# Connection.net
KiCad netlist of a schematic drawn in Altium Designer
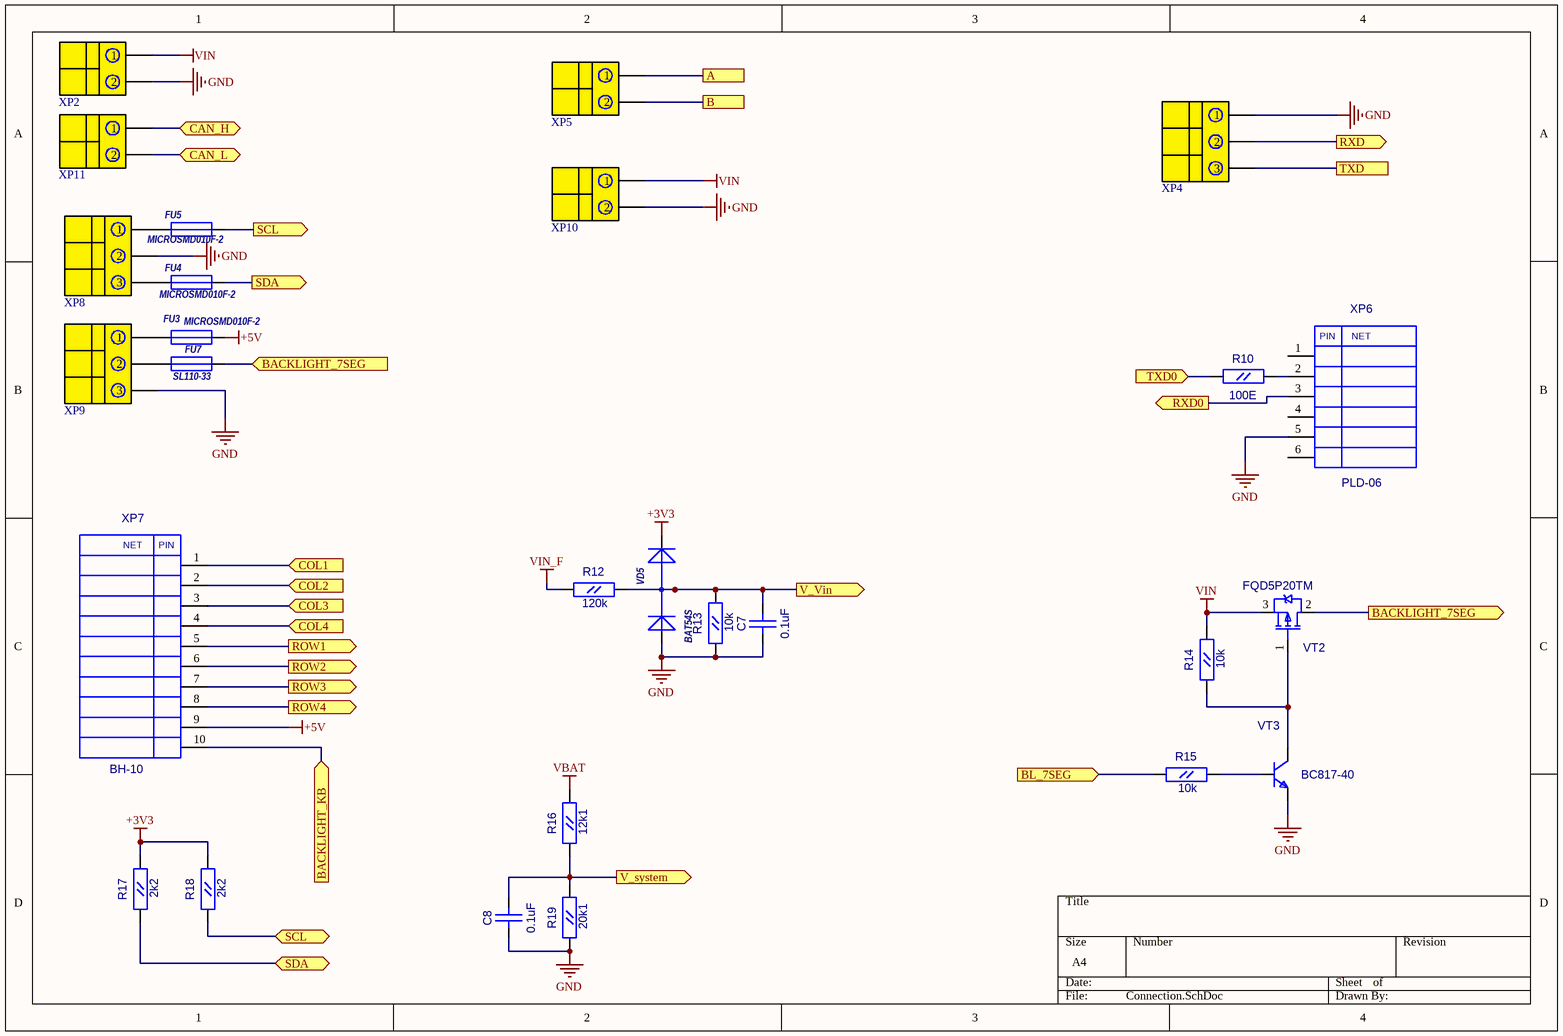
[diagram p0: Connection.SchDoc]

(export (version "E")
  (design (tool "Eeschema 10.0.6"))
  (components
    (comp (ref "C7")
      (value "0.1uF")
      (footprint "CC0603")
      (description "CC0603")
      (libsource (lib "gprs_modem_2") (part "CC0603"))
    )
    (comp (ref "C8")
      (value "0.1uF")
      (footprint "CC0603")
      (description "CC0603")
      (libsource (lib "gprs_modem_2") (part "CC0603"))
    )
    (comp (ref "FU3")
      (value "MICROSMD010F-2")
      (footprint "RC1210")
      (description "MICROSMD")
      (libsource (lib "gprs_modem_2") (part "MICROSMD"))
    )
    (comp (ref "FU4")
      (value "MICROSMD010F-2")
      (footprint "RC1210")
      (description "MICROSMD")
      (libsource (lib "gprs_modem_2") (part "MICROSMD"))
    )
    (comp (ref "FU5")
      (value "MICROSMD010F-2")
      (footprint "RC1210")
      (description "MICROSMD")
      (libsource (lib "gprs_modem_2") (part "MICROSMD"))
    )
    (comp (ref "FU7")
      (value "SL110-33")
      (footprint "FSMD2920")
      (description "FSMD150-2920")
      (libsource (lib "gprs_modem_2") (part "FSMD2920"))
    )
    (comp (ref "R10")
      (value "100E")
      (footprint "RC0603")
      (description "RC0603")
      (libsource (lib "gprs_modem_2") (part "RC0603"))
    )
    (comp (ref "R12")
      (value "120k")
      (footprint "RC0603")
      (description "RC0603")
      (libsource (lib "gprs_modem_2") (part "RC0603"))
    )
    (comp (ref "R13")
      (value "10k")
      (footprint "RC0603")
      (description "RC0603")
      (libsource (lib "gprs_modem_2") (part "RC0603"))
    )
    (comp (ref "R14")
      (value "10k")
      (footprint "RC0603")
      (description "RC0603")
      (libsource (lib "gprs_modem_2") (part "RC0603"))
    )
    (comp (ref "R15")
      (value "10k")
      (footprint "RC0603")
      (description "RC0603")
      (libsource (lib "gprs_modem_2") (part "RC0603"))
    )
    (comp (ref "R16")
      (value "12k1")
      (footprint "RC0603")
      (description "RC0603")
      (libsource (lib "gprs_modem_2") (part "RC0603"))
    )
    (comp (ref "R17")
      (value "2k2")
      (footprint "RC0603")
      (description "RC0603")
      (libsource (lib "gprs_modem_2") (part "RC0603"))
    )
    (comp (ref "R18")
      (value "2k2")
      (footprint "RC0603")
      (description "RC0603")
      (libsource (lib "gprs_modem_2") (part "RC0603"))
    )
    (comp (ref "R19")
      (value "20k1")
      (footprint "RC0603")
      (description "RC0603")
      (libsource (lib "gprs_modem_2") (part "RC0603"))
    )
    (comp (ref "VD5")
      (value "BAT54S")
      (footprint "SOT-23(GSD)")
      (description "1.0 Ampere General Purpose Rectifier")
      (libsource (lib "gprs_modem_2") (part "BAT54S"))
    )
    (comp (ref "VT2")
      (value "FQD5P20TM")
      (footprint "D-PAK(TO-252AA)")
      (description "HEXFET Power MOSFET")
      (libsource (lib "gprs_modem_2") (part "IRFR9220"))
    )
    (comp (ref "VT3")
      (value "BC817-40")
      (footprint "SOT-23(123)")
      (description "NPN 500ma transistor")
      (libsource (lib "gprs_modem_2") (part "BC846BLT1"))
    )
    (comp (ref "XP2")
      (value "DG330-2PIN")
      (footprint "DG330-2PIN")
      (libsource (lib "gprs_modem_2") (part "DG330-2PIN"))
    )
    (comp (ref "XP4")
      (value "DG330-3P")
      (footprint "DG330-3PIN")
      (libsource (lib "gprs_modem_2") (part "DG330-3PIN"))
    )
    (comp (ref "XP5")
      (value "DG330-2PIN")
      (footprint "DG330-2PIN")
      (libsource (lib "gprs_modem_2") (part "DG330-2PIN"))
    )
    (comp (ref "XP6")
      (value "PLD-06")
      (footprint "PIN6")
      (description "PLD06")
      (libsource (lib "gprs_modem_2") (part "PLD-06"))
    )
    (comp (ref "XP7") (value "BH-10") (footprint "BH-10") (libsource (lib "gprs_modem_2") (part "BH-10")))
    (comp (ref "XP8")
      (value "DG330-3PIN")
      (footprint "DG330-3PIN")
      (libsource (lib "gprs_modem_2") (part "DG330-3PIN"))
    )
    (comp (ref "XP9")
      (value "DG330-3PIN")
      (footprint "DG330-3PIN")
      (libsource (lib "gprs_modem_2") (part "DG330-3PIN"))
    )
    (comp (ref "XP10")
      (value "DG330-2PIN")
      (footprint "DG330-2PIN")
      (libsource (lib "gprs_modem_2") (part "DG330-2PIN"))
    )
    (comp (ref "XP11")
      (value "DG330-2PIN")
      (footprint "DG330-2PIN")
      (libsource (lib "gprs_modem_2") (part "DG330-2PIN"))
    )
  )
  (nets
    (net (code "1") (name "+3V3") (class "Default")
      (node (ref "R17") (pin "2") (pinfunction "B_2") (pintype "passive"))
      (node (ref "R18") (pin "2") (pinfunction "B_2") (pintype "passive"))
      (node (ref "VD5") (pin "2") (pinfunction "K_2") (pintype "passive"))
    )
    (net (code "2") (name "+5V") (class "Default")
      (node (ref "FU3") (pin "2") (pintype "passive"))
      (node (ref "XP7") (pin "9") (pinfunction "9_9") (pintype "passive"))
    )
    (net (code "3") (name "/A") (class "Default")
      (node (ref "XP5") (pin "1") (pinfunction "1_1") (pintype "passive"))
    )
    (net (code "4") (name "/B") (class "Default")
      (node (ref "XP5") (pin "2") (pinfunction "2_2") (pintype "passive"))
    )
    (net (code "5") (name "/BACKLIGHT_7SEG") (class "Default")
      (node (ref "FU7") (pin "2") (pintype "passive"))
      (node (ref "VT2") (pin "2") (pinfunction "D_2") (pintype "passive"))
    )
    (net (code "6") (name "/BACKLIGHT_KB") (class "Default")
      (node (ref "XP7") (pin "10") (pinfunction "10_10") (pintype "passive"))
    )
    (net (code "7") (name "/BL_7SEG") (class "Default")
      (node (ref "R15") (pin "1") (pinfunction "A_1") (pintype "passive"))
    )
    (net (code "8") (name "/CAN_H") (class "Default")
      (node (ref "XP11") (pin "1") (pinfunction "1_1") (pintype "passive"))
    )
    (net (code "9") (name "/CAN_L") (class "Default")
      (node (ref "XP11") (pin "2") (pinfunction "2_2") (pintype "passive"))
    )
    (net (code "10") (name "/COL1") (class "Default")
      (node (ref "XP7") (pin "1") (pinfunction "1_1") (pintype "passive"))
    )
    (net (code "11") (name "/COL2") (class "Default")
      (node (ref "XP7") (pin "2") (pinfunction "2_2") (pintype "passive"))
    )
    (net (code "12") (name "/COL3") (class "Default")
      (node (ref "XP7") (pin "3") (pinfunction "3_3") (pintype "passive"))
    )
    (net (code "13") (name "/COL4") (class "Default")
      (node (ref "XP7") (pin "4") (pinfunction "4_4") (pintype "passive"))
    )
    (net (code "14") (name "/ROW1") (class "Default")
      (node (ref "XP7") (pin "5") (pinfunction "5_5") (pintype "passive"))
    )
    (net (code "15") (name "/ROW2") (class "Default")
      (node (ref "XP7") (pin "6") (pinfunction "6_6") (pintype "passive"))
    )
    (net (code "16") (name "/ROW3") (class "Default")
      (node (ref "XP7") (pin "7") (pinfunction "7_7") (pintype "passive"))
    )
    (net (code "17") (name "/ROW4") (class "Default")
      (node (ref "XP7") (pin "8") (pinfunction "8_8") (pintype "passive"))
    )
    (net (code "18") (name "/RXD") (class "Default")
      (node (ref "XP4") (pin "2") (pinfunction "2_2") (pintype "passive"))
    )
    (net (code "19") (name "/RXD0") (class "Default")
      (node (ref "XP6") (pin "3") (pinfunction "3_3") (pintype "passive"))
    )
    (net (code "20") (name "/SCL") (class "Default")
      (node (ref "FU5") (pin "2") (pintype "passive"))
      (node (ref "R18") (pin "1") (pinfunction "A_1") (pintype "passive"))
    )
    (net (code "21") (name "/SDA") (class "Default")
      (node (ref "FU4") (pin "2") (pintype "passive"))
      (node (ref "R17") (pin "1") (pinfunction "A_1") (pintype "passive"))
    )
    (net (code "22") (name "/TXD") (class "Default")
      (node (ref "XP4") (pin "3") (pinfunction "3_3") (pintype "passive"))
    )
    (net (code "23") (name "/TXD0") (class "Default")
      (node (ref "R10") (pin "1") (pinfunction "A_1") (pintype "passive"))
    )
    (net (code "24") (name "/V_Vin") (class "Default")
      (node (ref "C7") (pin "2") (pinfunction "B_2") (pintype "passive"))
      (node (ref "R12") (pin "2") (pinfunction "B_2") (pintype "passive"))
      (node (ref "R13") (pin "2") (pinfunction "B_2") (pintype "passive"))
      (node (ref "VD5") (pin "3") (pinfunction "AK_3") (pintype "passive"))
    )
    (net (code "25") (name "/V_system") (class "Default")
      (node (ref "C8") (pin "2") (pinfunction "B_2") (pintype "passive"))
      (node (ref "R16") (pin "1") (pinfunction "A_1") (pintype "passive"))
      (node (ref "R19") (pin "2") (pinfunction "B_2") (pintype "passive"))
    )
    (net (code "26") (name "GND") (class "Default")
      (node (ref "C7") (pin "1") (pinfunction "A_1") (pintype "passive"))
      (node (ref "C8") (pin "1") (pinfunction "A_1") (pintype "passive"))
      (node (ref "R13") (pin "1") (pinfunction "A_1") (pintype "passive"))
      (node (ref "R19") (pin "1") (pinfunction "A_1") (pintype "passive"))
      (node (ref "VD5") (pin "1") (pinfunction "A_1") (pintype "passive"))
      (node (ref "VT3") (pin "2") (pinfunction "E_2") (pintype "passive"))
      (node (ref "XP10") (pin "2") (pinfunction "2_2") (pintype "passive"))
      (node (ref "XP2") (pin "2") (pinfunction "2_2") (pintype "passive"))
      (node (ref "XP4") (pin "1") (pinfunction "1_1") (pintype "passive"))
      (node (ref "XP6") (pin "5") (pinfunction "5_5") (pintype "passive"))
      (node (ref "XP8") (pin "2") (pinfunction "2_2") (pintype "passive"))
      (node (ref "XP9") (pin "3") (pinfunction "3_3") (pintype "passive"))
    )
    (net (code "27") (name "Net-(FU3-Pad1)") (class "Default")
      (node (ref "FU3") (pin "1") (pintype "passive"))
      (node (ref "XP9") (pin "1") (pinfunction "1_1") (pintype "passive"))
    )
    (net (code "28") (name "Net-(FU4-Pad1)") (class "Default")
      (node (ref "FU4") (pin "1") (pintype "passive"))
      (node (ref "XP8") (pin "3") (pinfunction "3_3") (pintype "passive"))
    )
    (net (code "29") (name "Net-(FU5-Pad1)") (class "Default")
      (node (ref "FU5") (pin "1") (pintype "passive"))
      (node (ref "XP8") (pin "1") (pinfunction "1_1") (pintype "passive"))
    )
    (net (code "30") (name "Net-(FU7-Pad1)") (class "Default")
      (node (ref "FU7") (pin "1") (pintype "passive"))
      (node (ref "XP9") (pin "2") (pinfunction "2_2") (pintype "passive"))
    )
    (net (code "31") (name "Net-(R10-B)") (class "Default")
      (node (ref "R10") (pin "2") (pinfunction "B_2") (pintype "passive"))
      (node (ref "XP6") (pin "2") (pinfunction "2_2") (pintype "passive"))
    )
    (net (code "32") (name "Net-(R14-A)") (class "Default")
      (node (ref "R14") (pin "1") (pinfunction "A_1") (pintype "passive"))
      (node (ref "VT2") (pin "1") (pinfunction "G_1") (pintype "passive"))
      (node (ref "VT3") (pin "3") (pinfunction "C_3") (pintype "passive"))
    )
    (net (code "33") (name "Net-(R15-B)") (class "Default")
      (node (ref "R15") (pin "2") (pinfunction "B_2") (pintype "passive"))
      (node (ref "VT3") (pin "1") (pinfunction "B_1") (pintype "passive"))
    )
    (net (code "34") (name "VBAT") (class "Default")
      (node (ref "R16") (pin "2") (pinfunction "B_2") (pintype "passive"))
    )
    (net (code "35") (name "VIN") (class "Default")
      (node (ref "R14") (pin "2") (pinfunction "B_2") (pintype "passive"))
      (node (ref "VT2") (pin "3") (pinfunction "S_3") (pintype "passive"))
      (node (ref "XP10") (pin "1") (pinfunction "1_1") (pintype "passive"))
      (node (ref "XP2") (pin "1") (pinfunction "1_1") (pintype "passive"))
    )
    (net (code "36") (name "VIN_F") (class "Default")
      (node (ref "R12") (pin "1") (pinfunction "A_1") (pintype "passive"))
    )
    (net (code "37") (name "unconnected-(XP6-Pad1)") (class "Default")
      (node (ref "XP6") (pin "1") (pinfunction "1_1") (pintype "passive"))
    )
    (net (code "38") (name "unconnected-(XP6-Pad4)") (class "Default")
      (node (ref "XP6") (pin "4") (pinfunction "4_4") (pintype "passive"))
    )
    (net (code "39") (name "unconnected-(XP6-Pad6)") (class "Default")
      (node (ref "XP6") (pin "6") (pinfunction "6_6") (pintype "passive"))
    )
  )
)
